# SwitchBoard.net
KiCad netlist of a schematic drawn in EAGLE
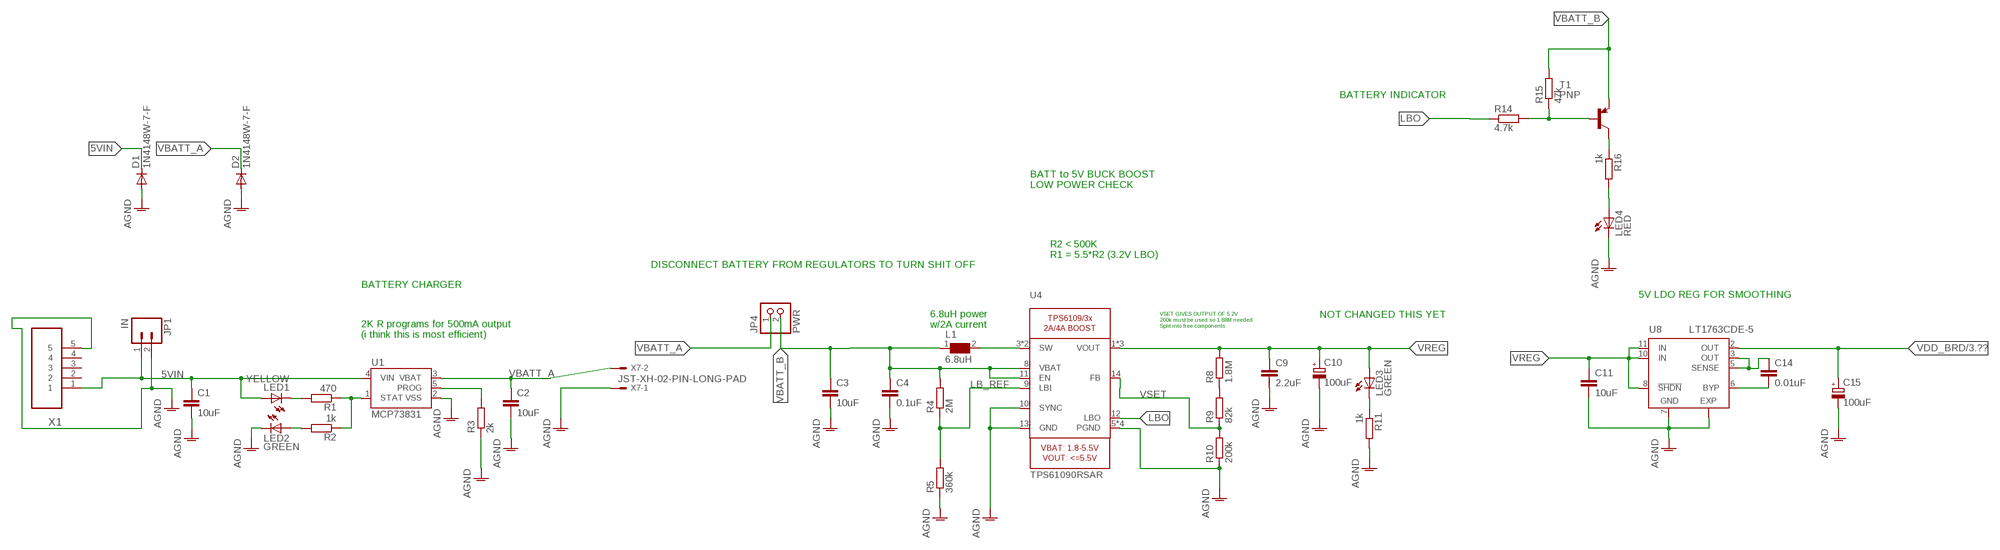
[diagram p0: schematic, sheet 1]
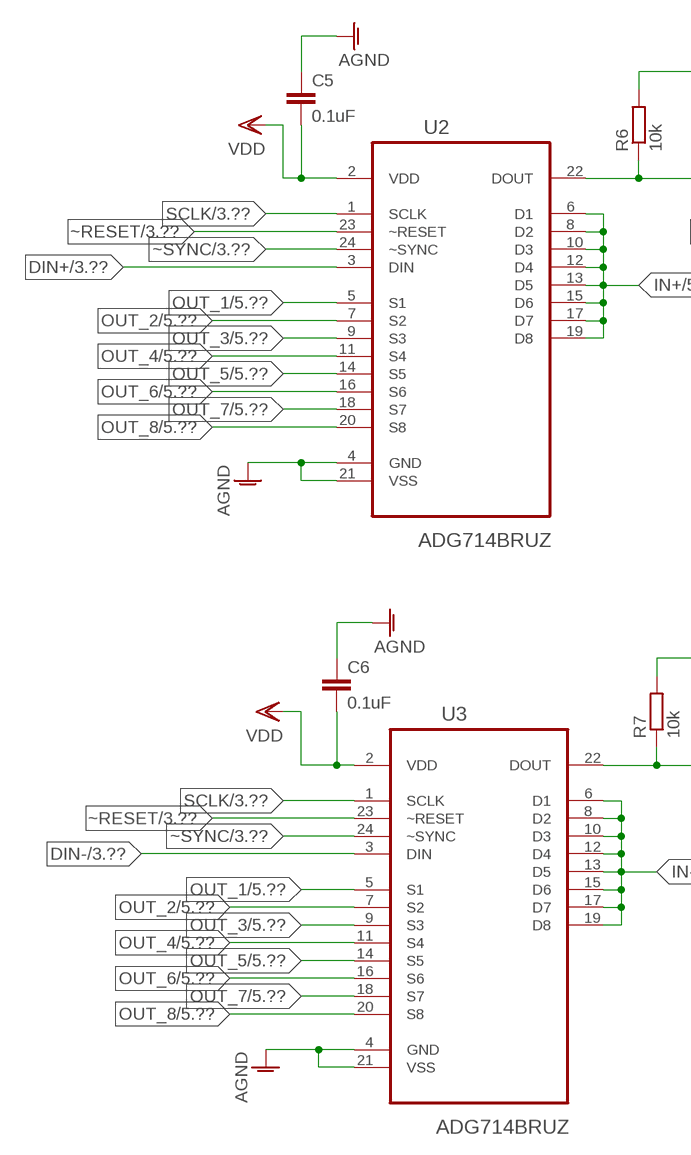
[diagram p1: schematic, sheet 2, part 1 of 2]
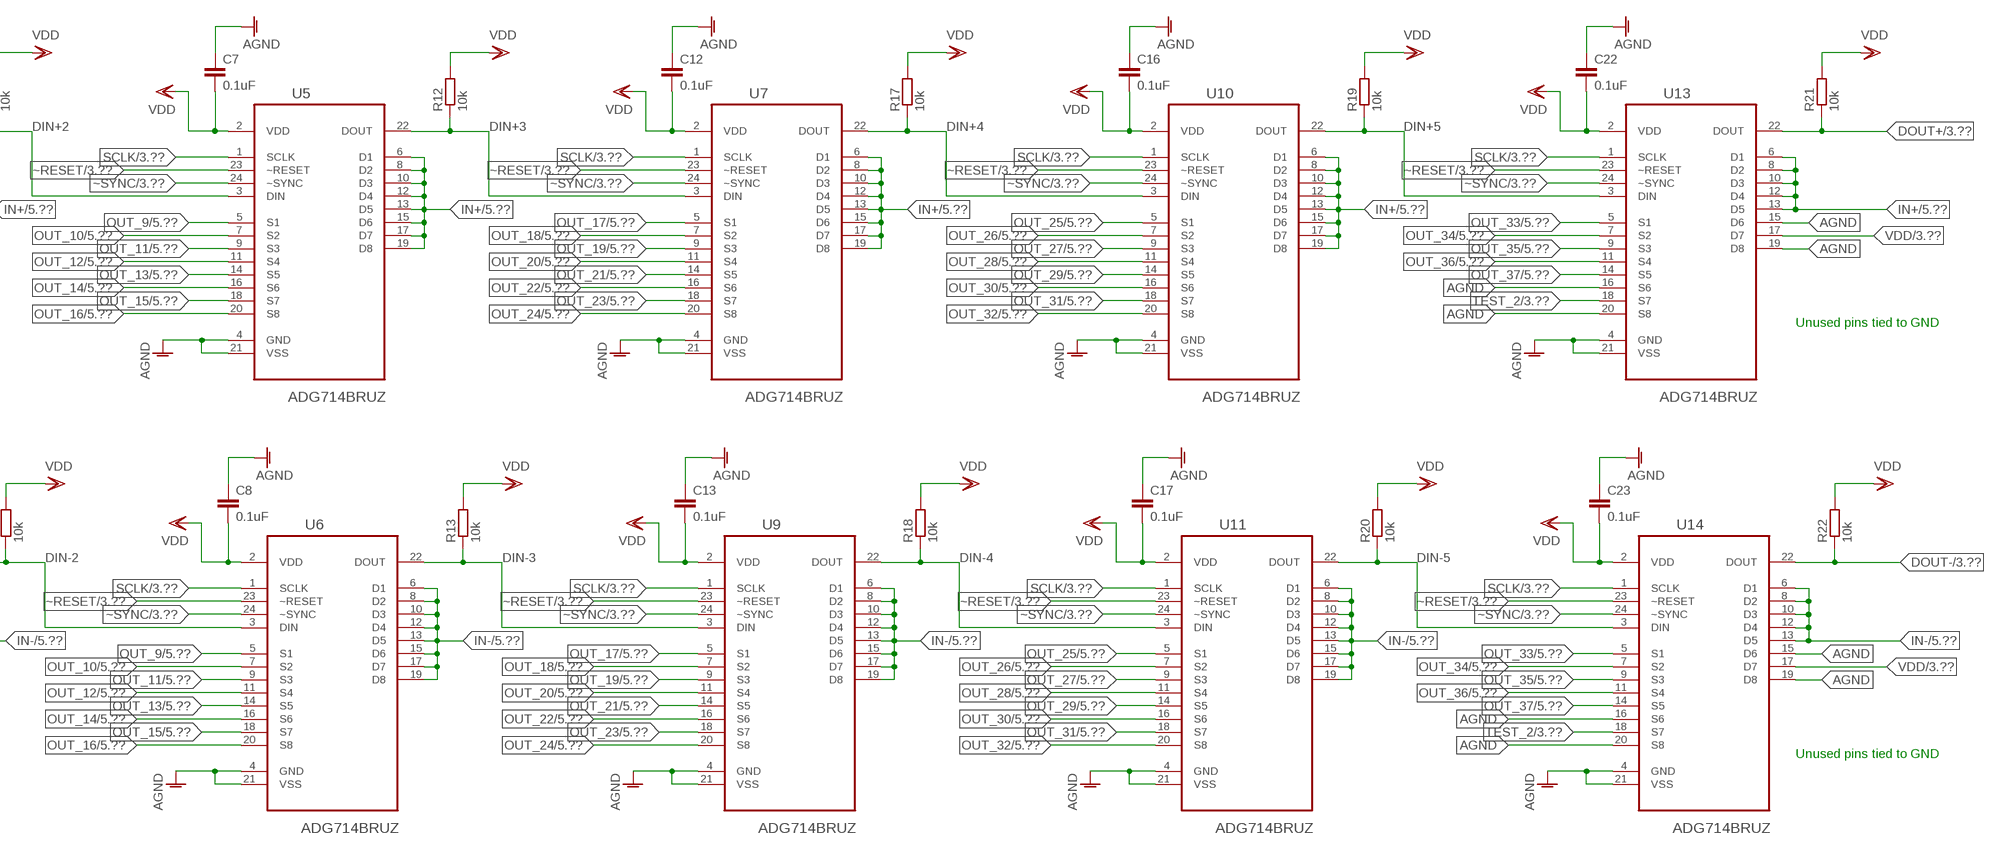
[diagram p2: schematic, sheet 2, part 2 of 2]
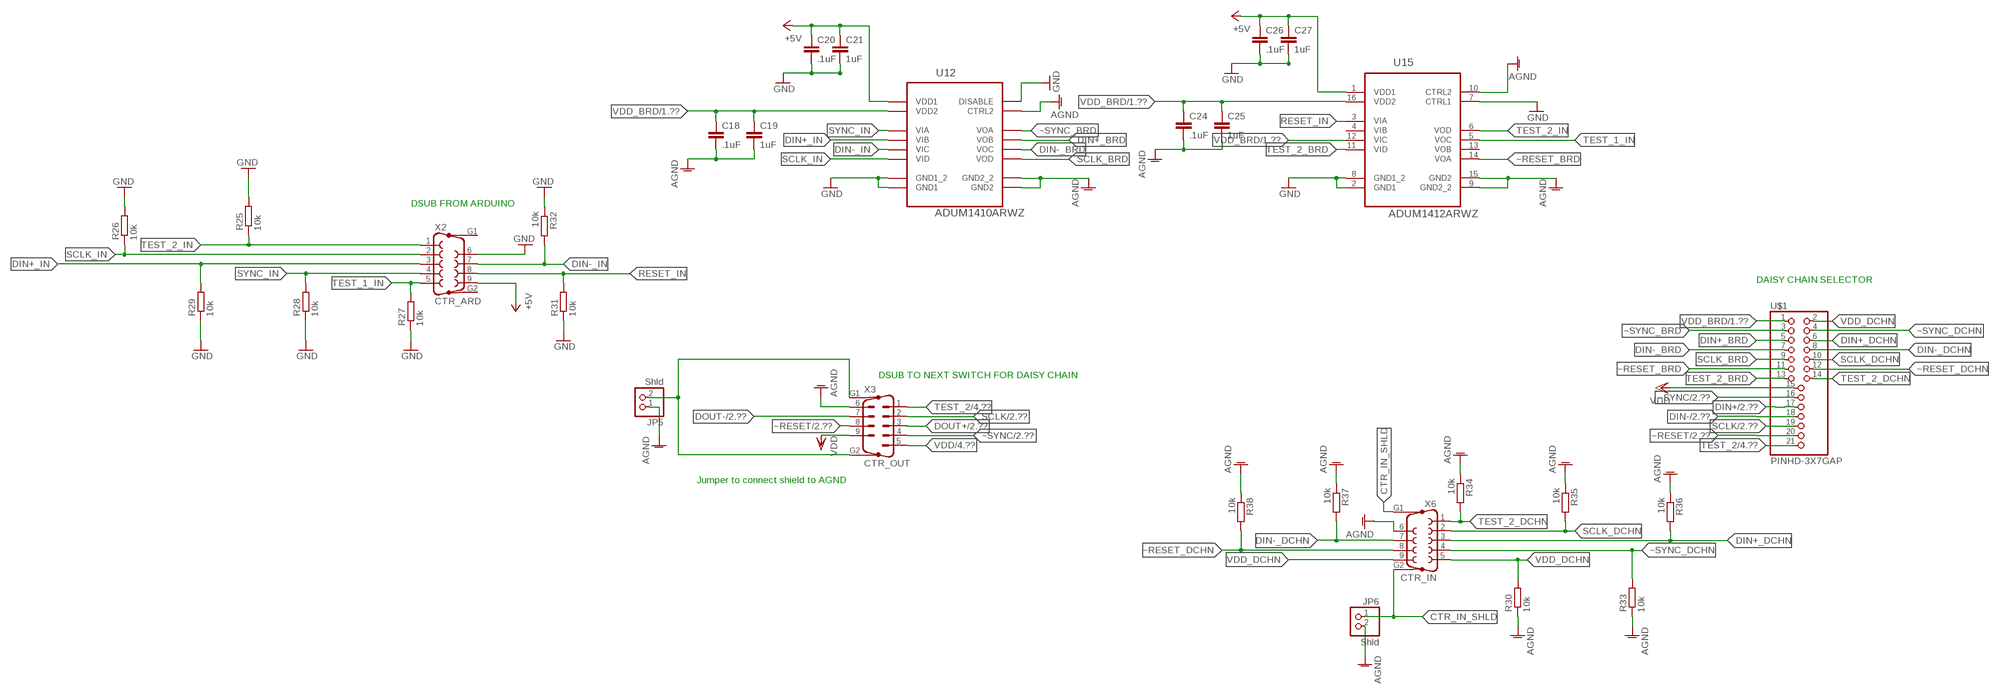
[diagram p3: schematic, sheet 3]
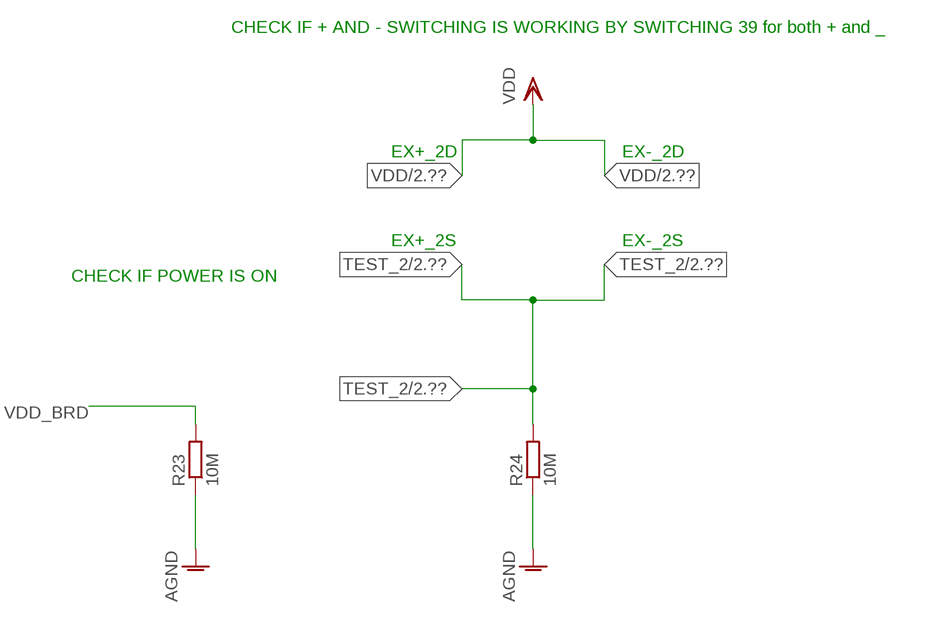
[diagram p4: schematic, sheet 4]
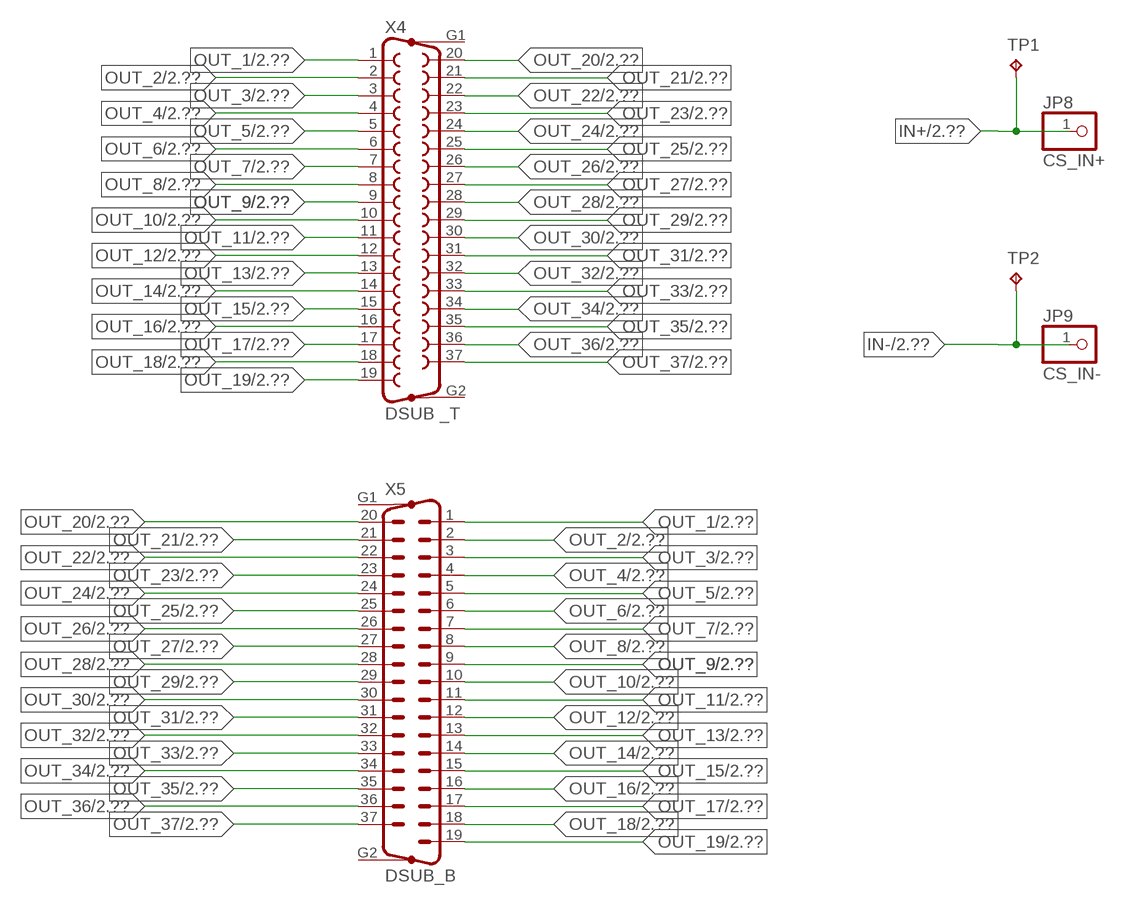
[diagram p5: schematic, sheet 5]

(export (version "E")
  (design (tool "Eeschema 10.0.6"))
  (components
    (comp (ref "JP8")
      (value "CS_IN+")
      (footprint "eagle-import:1X01")
      (libsource (lib "eagle-import") (part "PINHD-1X1"))
    )
    (comp (ref "JP9")
      (value "CS_IN-")
      (footprint "eagle-import:1X01")
      (libsource (lib "eagle-import") (part "PINHD-1X1"))
    )
    (comp (ref "TP1")
      (value "TPPAD1-20")
      (footprint "eagle-import:P1-20")
      (libsource (lib "eagle-import") (part "TPPAD1-20"))
    )
    (comp (ref "TP2")
      (value "TPPAD1-20")
      (footprint "eagle-import:P1-20")
      (libsource (lib "eagle-import") (part "TPPAD1-20"))
    )
    (comp (ref "X4")
      (value "DSUB _T")
      (footprint "eagle-import:F37HP")
      (libsource (lib "eagle-import") (part "F37HP"))
    )
    (comp (ref "X5")
      (value "DSUB_B")
      (footprint "eagle-import:M37HP")
      (libsource (lib "eagle-import") (part "M37HP"))
    )
    (comp (ref "R23")
      (value "10M")
      (footprint "eagle-import:M0805")
      (libsource (lib "eagle-import") (part "R-EU_M0805"))
    )
    (comp (ref "R24")
      (value "10M")
      (footprint "eagle-import:M0805")
      (libsource (lib "eagle-import") (part "R-EU_M0805"))
    )
    (comp (ref "C1")
      (value "10uF")
      (footprint "eagle-import:C0805")
      (libsource (lib "eagle-import") (part "C-EUC0805"))
    )
    (comp (ref "C2")
      (value "10uF")
      (footprint "eagle-import:C0805")
      (libsource (lib "eagle-import") (part "C-EUC0805"))
    )
    (comp (ref "C3")
      (value "10uF")
      (footprint "eagle-import:C0805")
      (libsource (lib "eagle-import") (part "C-EUC0805"))
    )
    (comp (ref "C4")
      (value "0.1uF")
      (footprint "eagle-import:C0805")
      (libsource (lib "eagle-import") (part "C-EUC0805"))
    )
    (comp (ref "C9")
      (value "2.2uF")
      (footprint "eagle-import:C0805")
      (libsource (lib "eagle-import") (part "C-EUC0805"))
    )
    (comp (ref "C10")
      (value "100uF")
      (footprint "eagle-import:CT6032")
      (libsource (lib "eagle-import") (part "CPOL-EUCT6032"))
    )
    (comp (ref "C11")
      (value "10uF")
      (footprint "eagle-import:C0805")
      (libsource (lib "eagle-import") (part "C-EUC0805"))
    )
    (comp (ref "C14")
      (value "0.01uF")
      (footprint "eagle-import:C0805")
      (libsource (lib "eagle-import") (part "C-EUC0805"))
    )
    (comp (ref "C15")
      (value "100uF")
      (footprint "eagle-import:CT6032")
      (libsource (lib "eagle-import") (part "CPOL-EUCT6032"))
    )
    (comp (ref "D1")
      (value "1N4148W-7-F")
      (footprint "eagle-import:SOD123")
      (libsource (lib "eagle-import") (part "DIODE-SOD123"))
    )
    (comp (ref "D2")
      (value "1N4148W-7-F")
      (footprint "eagle-import:SOD123")
      (libsource (lib "eagle-import") (part "DIODE-SOD123"))
    )
    (comp (ref "JP1")
      (value "IN")
      (footprint "eagle-import:1X02")
      (libsource (lib "eagle-import") (part "M02PTH"))
    )
    (comp (ref "JP4")
      (value "PWR")
      (footprint "eagle-import:1X02")
      (libsource (lib "eagle-import") (part "PINHD-1X2"))
    )
    (comp (ref "L1")
      (value "6.8uH")
      (footprint "eagle-import:WE-PD_7332_7345_PLASTIC_BASE")
      (fields (field (name "MPN") "7447779006"))
      (libsource (lib "eagle-import") (part "WE-PD_7332/7345_PLASTIC_BASE-7447779006"))
    )
    (comp (ref "LED1")
      (value "YELLOW")
      (footprint "eagle-import:SML0805")
      (libsource (lib "eagle-import") (part "LEDSML0805"))
    )
    (comp (ref "LED2")
      (value "GREEN")
      (footprint "eagle-import:SML0805")
      (libsource (lib "eagle-import") (part "LEDSML0805"))
    )
    (comp (ref "LED3")
      (value "GREEN")
      (footprint "eagle-import:SML0805")
      (libsource (lib "eagle-import") (part "LEDSML0805"))
    )
    (comp (ref "LED4")
      (value "RED")
      (footprint "eagle-import:SML0805")
      (libsource (lib "eagle-import") (part "LEDSML0805"))
    )
    (comp (ref "R1")
      (value "470")
      (footprint "eagle-import:M0805")
      (libsource (lib "eagle-import") (part "R-EU_M0805"))
    )
    (comp (ref "R2")
      (value "1k")
      (footprint "eagle-import:M0805")
      (libsource (lib "eagle-import") (part "R-EU_M0805"))
    )
    (comp (ref "R3")
      (value "2k")
      (footprint "eagle-import:M0805")
      (libsource (lib "eagle-import") (part "R-EU_M0805"))
    )
    (comp (ref "R4")
      (value "2M")
      (footprint "eagle-import:M0805")
      (libsource (lib "eagle-import") (part "R-EU_M0805"))
    )
    (comp (ref "R5")
      (value "360k")
      (footprint "eagle-import:M0805")
      (libsource (lib "eagle-import") (part "R-EU_M0805"))
    )
    (comp (ref "R8")
      (value "1.8M")
      (footprint "eagle-import:M0805")
      (libsource (lib "eagle-import") (part "R-EU_M0805"))
    )
    (comp (ref "R9")
      (value "82k")
      (footprint "eagle-import:M0805")
      (libsource (lib "eagle-import") (part "R-EU_M0805"))
    )
    (comp (ref "R10")
      (value "200k")
      (footprint "eagle-import:M0805")
      (libsource (lib "eagle-import") (part "R-EU_M0805"))
    )
    (comp (ref "R11")
      (value "1k")
      (footprint "eagle-import:M0805")
      (libsource (lib "eagle-import") (part "R-EU_M0805"))
    )
    (comp (ref "R14")
      (value "4.7k")
      (footprint "eagle-import:M0805")
      (libsource (lib "eagle-import") (part "R-EU_M0805"))
    )
    (comp (ref "R15")
      (value "47k")
      (footprint "eagle-import:M0805")
      (libsource (lib "eagle-import") (part "R-EU_M0805"))
    )
    (comp (ref "R16")
      (value "1k")
      (footprint "eagle-import:M0805")
      (libsource (lib "eagle-import") (part "R-EU_M0805"))
    )
    (comp (ref "T1")
      (value "PNP")
      (footprint "eagle-import:SOT23-BEC")
      (libsource (lib "eagle-import") (part "-PNP-SOT23-BECBC807-40"))
    )
    (comp (ref "U1")
      (value "MCP73831")
      (footprint "eagle-import:SOT23-5")
      (libsource (lib "eagle-import") (part "MCP73831"))
    )
    (comp (ref "U4")
      (value "TPS61090RSAR")
      (footprint "eagle-import:QFN16-4X4")
      (libsource (lib "eagle-import") (part "VREG_TPS6103XSPARKFUNVERSION"))
    )
    (comp (ref "U8")
      (value "LT1763CDE-5")
      (footprint "eagle-import:DFN12")
      (libsource (lib "eagle-import") (part "LT1763CDE-5"))
    )
    (comp (ref "X1")
      (value "47346-0001")
      (footprint "eagle-import:MOLEX_47346-0001")
      (libsource (lib "eagle-import") (part "47346-0001"))
    )
    (comp (ref "X7")
      (value "JST-XH-02-PIN-LONG-PAD")
      (footprint "eagle-import:JST-XH-02-PACKAGE-LONG-PAD")
      (libsource (lib "eagle-import") (part "JST-XH-02-PIN-LONG-PAD"))
    )
    (comp (ref "C5")
      (value "0.1uF")
      (footprint "eagle-import:C0805")
      (libsource (lib "eagle-import") (part "C-EUC0805"))
    )
    (comp (ref "C6")
      (value "0.1uF")
      (footprint "eagle-import:C0805")
      (libsource (lib "eagle-import") (part "C-EUC0805"))
    )
    (comp (ref "C7")
      (value "0.1uF")
      (footprint "eagle-import:C0805")
      (libsource (lib "eagle-import") (part "C-EUC0805"))
    )
    (comp (ref "C8")
      (value "0.1uF")
      (footprint "eagle-import:C0805")
      (libsource (lib "eagle-import") (part "C-EUC0805"))
    )
    (comp (ref "C12")
      (value "0.1uF")
      (footprint "eagle-import:C0805")
      (libsource (lib "eagle-import") (part "C-EUC0805"))
    )
    (comp (ref "C13")
      (value "0.1uF")
      (footprint "eagle-import:C0805")
      (libsource (lib "eagle-import") (part "C-EUC0805"))
    )
    (comp (ref "C16")
      (value "0.1uF")
      (footprint "eagle-import:C0805")
      (libsource (lib "eagle-import") (part "C-EUC0805"))
    )
    (comp (ref "C17")
      (value "0.1uF")
      (footprint "eagle-import:C0805")
      (libsource (lib "eagle-import") (part "C-EUC0805"))
    )
    (comp (ref "C22")
      (value "0.1uF")
      (footprint "eagle-import:C0805")
      (libsource (lib "eagle-import") (part "C-EUC0805"))
    )
    (comp (ref "C23")
      (value "0.1uF")
      (footprint "eagle-import:C0805")
      (libsource (lib "eagle-import") (part "C-EUC0805"))
    )
    (comp (ref "R6")
      (value "10k")
      (footprint "eagle-import:M0805")
      (libsource (lib "eagle-import") (part "R-EU_M0805"))
    )
    (comp (ref "R7")
      (value "10k")
      (footprint "eagle-import:M0805")
      (libsource (lib "eagle-import") (part "R-EU_M0805"))
    )
    (comp (ref "R12")
      (value "10k")
      (footprint "eagle-import:M0805")
      (libsource (lib "eagle-import") (part "R-EU_M0805"))
    )
    (comp (ref "R13")
      (value "10k")
      (footprint "eagle-import:M0805")
      (libsource (lib "eagle-import") (part "R-EU_M0805"))
    )
    (comp (ref "R17")
      (value "10k")
      (footprint "eagle-import:M0805")
      (libsource (lib "eagle-import") (part "R-EU_M0805"))
    )
    (comp (ref "R18")
      (value "10k")
      (footprint "eagle-import:M0805")
      (libsource (lib "eagle-import") (part "R-EU_M0805"))
    )
    (comp (ref "R19")
      (value "10k")
      (footprint "eagle-import:M0805")
      (libsource (lib "eagle-import") (part "R-EU_M0805"))
    )
    (comp (ref "R20")
      (value "10k")
      (footprint "eagle-import:M0805")
      (libsource (lib "eagle-import") (part "R-EU_M0805"))
    )
    (comp (ref "R21")
      (value "10k")
      (footprint "eagle-import:M0805")
      (libsource (lib "eagle-import") (part "R-EU_M0805"))
    )
    (comp (ref "R22")
      (value "10k")
      (footprint "eagle-import:M0805")
      (libsource (lib "eagle-import") (part "R-EU_M0805"))
    )
    (comp (ref "U2")
      (value "ADG714BRUZ")
      (footprint "eagle-import:SOP65P640X120-24N")
      (libsource (lib "eagle-import") (part "ADG714BRUZ"))
    )
    (comp (ref "U3")
      (value "ADG714BRUZ")
      (footprint "eagle-import:SOP65P640X120-24N")
      (libsource (lib "eagle-import") (part "ADG714BRUZ"))
    )
    (comp (ref "U5")
      (value "ADG714BRUZ")
      (footprint "eagle-import:SOP65P640X120-24N")
      (libsource (lib "eagle-import") (part "ADG714BRUZ"))
    )
    (comp (ref "U6")
      (value "ADG714BRUZ")
      (footprint "eagle-import:SOP65P640X120-24N")
      (libsource (lib "eagle-import") (part "ADG714BRUZ"))
    )
    (comp (ref "U7")
      (value "ADG714BRUZ")
      (footprint "eagle-import:SOP65P640X120-24N")
      (libsource (lib "eagle-import") (part "ADG714BRUZ"))
    )
    (comp (ref "U9")
      (value "ADG714BRUZ")
      (footprint "eagle-import:SOP65P640X120-24N")
      (libsource (lib "eagle-import") (part "ADG714BRUZ"))
    )
    (comp (ref "U10")
      (value "ADG714BRUZ")
      (footprint "eagle-import:SOP65P640X120-24N")
      (libsource (lib "eagle-import") (part "ADG714BRUZ"))
    )
    (comp (ref "U11")
      (value "ADG714BRUZ")
      (footprint "eagle-import:SOP65P640X120-24N")
      (libsource (lib "eagle-import") (part "ADG714BRUZ"))
    )
    (comp (ref "U13")
      (value "ADG714BRUZ")
      (footprint "eagle-import:SOP65P640X120-24N")
      (libsource (lib "eagle-import") (part "ADG714BRUZ"))
    )
    (comp (ref "U14")
      (value "ADG714BRUZ")
      (footprint "eagle-import:SOP65P640X120-24N")
      (libsource (lib "eagle-import") (part "ADG714BRUZ"))
    )
    (comp (ref "C18")
      (value ".1uF")
      (footprint "eagle-import:C0805")
      (libsource (lib "eagle-import") (part "C-EUC0805"))
    )
    (comp (ref "C19")
      (value "1uF")
      (footprint "eagle-import:C0805")
      (libsource (lib "eagle-import") (part "C-EUC0805"))
    )
    (comp (ref "C20")
      (value ".1uF")
      (footprint "eagle-import:C0805")
      (libsource (lib "eagle-import") (part "C-EUC0805"))
    )
    (comp (ref "C21")
      (value "1uF")
      (footprint "eagle-import:C0805")
      (libsource (lib "eagle-import") (part "C-EUC0805"))
    )
    (comp (ref "C24")
      (value ".1uF")
      (footprint "eagle-import:C0805")
      (libsource (lib "eagle-import") (part "C-EUC0805"))
    )
    (comp (ref "C25")
      (value "1uF")
      (footprint "eagle-import:C0805")
      (libsource (lib "eagle-import") (part "C-EUC0805"))
    )
    (comp (ref "C26")
      (value ".1uF")
      (footprint "eagle-import:C0805")
      (libsource (lib "eagle-import") (part "C-EUC0805"))
    )
    (comp (ref "C27")
      (value "1uF")
      (footprint "eagle-import:C0805")
      (libsource (lib "eagle-import") (part "C-EUC0805"))
    )
    (comp (ref "JP5")
      (value "Shld")
      (footprint "eagle-import:1X02")
      (libsource (lib "eagle-import") (part "PINHD-1X2"))
    )
    (comp (ref "JP6")
      (value "Shld")
      (footprint "eagle-import:1X02")
      (libsource (lib "eagle-import") (part "PINHD-1X2"))
    )
    (comp (ref "R25")
      (value "10k")
      (footprint "eagle-import:R0402")
      (libsource (lib "eagle-import") (part "R-EU_R0402"))
    )
    (comp (ref "R26")
      (value "10k")
      (footprint "eagle-import:R0402")
      (libsource (lib "eagle-import") (part "R-EU_R0402"))
    )
    (comp (ref "R27")
      (value "10k")
      (footprint "eagle-import:R0402")
      (libsource (lib "eagle-import") (part "R-EU_R0402"))
    )
    (comp (ref "R28")
      (value "10k")
      (footprint "eagle-import:R0402")
      (libsource (lib "eagle-import") (part "R-EU_R0402"))
    )
    (comp (ref "R29")
      (value "10k")
      (footprint "eagle-import:R0402")
      (libsource (lib "eagle-import") (part "R-EU_R0402"))
    )
    (comp (ref "R30")
      (value "10k")
      (footprint "eagle-import:R0402")
      (libsource (lib "eagle-import") (part "R-EU_R0402"))
    )
    (comp (ref "R31")
      (value "10k")
      (footprint "eagle-import:R0402")
      (libsource (lib "eagle-import") (part "R-EU_R0402"))
    )
    (comp (ref "R32")
      (value "10k")
      (footprint "eagle-import:R0402")
      (libsource (lib "eagle-import") (part "R-EU_R0402"))
    )
    (comp (ref "R33")
      (value "10k")
      (footprint "eagle-import:R0402")
      (libsource (lib "eagle-import") (part "R-EU_R0402"))
    )
    (comp (ref "R34")
      (value "10k")
      (footprint "eagle-import:R0402")
      (libsource (lib "eagle-import") (part "R-EU_R0402"))
    )
    (comp (ref "R35")
      (value "10k")
      (footprint "eagle-import:R0402")
      (libsource (lib "eagle-import") (part "R-EU_R0402"))
    )
    (comp (ref "R36")
      (value "10k")
      (footprint "eagle-import:R0402")
      (libsource (lib "eagle-import") (part "R-EU_R0402"))
    )
    (comp (ref "R37")
      (value "10k")
      (footprint "eagle-import:R0402")
      (libsource (lib "eagle-import") (part "R-EU_R0402"))
    )
    (comp (ref "R38")
      (value "10k")
      (footprint "eagle-import:R0402")
      (libsource (lib "eagle-import") (part "R-EU_R0402"))
    )
    (comp (ref "U$1")
      (value "PINHD-3X7GAP")
      (footprint "eagle-import:3X07")
      (libsource (lib "eagle-import") (part "PINHD-3X7GAP"))
    )
    (comp (ref "U12")
      (value "ADUM1410ARWZ")
      (footprint "eagle-import:SOIC127P1032X265-16N")
      (libsource (lib "eagle-import") (part "ADUM1410ARWZ"))
    )
    (comp (ref "U15")
      (value "ADUM1412ARWZ")
      (footprint "eagle-import:SOIC127P1032X265-16N")
      (libsource (lib "eagle-import") (part "ADUM1412ARWZ"))
    )
    (comp (ref "X2")
      (value "CTR_ARD")
      (footprint "eagle-import:F09HP")
      (libsource (lib "eagle-import") (part "F09HP"))
    )
    (comp (ref "X3")
      (value "CTR_OUT")
      (footprint "eagle-import:M09HP")
      (libsource (lib "eagle-import") (part "M09HP"))
    )
    (comp (ref "X6")
      (value "CTR_IN")
      (footprint "eagle-import:F09HP")
      (libsource (lib "eagle-import") (part "F09HP"))
    )
  )
  (nets
    (net (code "1") (name "+5V") (class "Default")
      (node (ref "C20") (pin "1") (pinfunction "1_1") (pintype "passive"))
      (node (ref "C21") (pin "1") (pinfunction "1_1") (pintype "passive"))
      (node (ref "C26") (pin "1") (pinfunction "1_1") (pintype "passive"))
      (node (ref "C27") (pin "1") (pinfunction "1_1") (pintype "passive"))
      (node (ref "U12") (pin "1") (pinfunction "VDD1_1") (pintype "power_in"))
      (node (ref "U15") (pin "1") (pinfunction "VDD1_1") (pintype "power_in"))
      (node (ref "X2") (pin "9") (pinfunction "9_9") (pintype "passive"))
    )
    (net (code "2") (name "5VIN") (class "Default")
      (node (ref "C1") (pin "1") (pinfunction "1_1") (pintype "passive"))
      (node (ref "D1") (pin "C") (pinfunction "C_C") (pintype "passive"))
      (node (ref "JP1") (pin "1") (pinfunction "1_1") (pintype "passive"))
      (node (ref "LED1") (pin "A") (pinfunction "A_A") (pintype "passive"))
      (node (ref "U1") (pin "4") (pinfunction "VIN_4") (pintype "power_in"))
      (node (ref "X1") (pin "1") (pinfunction "1_1") (pintype "input"))
    )
    (net (code "3") (name "AGND") (class "Default")
      (node (ref "C1") (pin "2") (pinfunction "2_2") (pintype "passive"))
      (node (ref "C10") (pin "-") (pinfunction "-_-") (pintype "passive"))
      (node (ref "C11") (pin "2") (pinfunction "2_2") (pintype "passive"))
      (node (ref "C12") (pin "1") (pinfunction "1_1") (pintype "passive"))
      (node (ref "C13") (pin "1") (pinfunction "1_1") (pintype "passive"))
      (node (ref "C15") (pin "-") (pinfunction "-_-") (pintype "passive"))
      (node (ref "C16") (pin "1") (pinfunction "1_1") (pintype "passive"))
      (node (ref "C17") (pin "1") (pinfunction "1_1") (pintype "passive"))
      (node (ref "C18") (pin "2") (pinfunction "2_2") (pintype "passive"))
      (node (ref "C19") (pin "2") (pinfunction "2_2") (pintype "passive"))
      (node (ref "C2") (pin "2") (pinfunction "2_2") (pintype "passive"))
      (node (ref "C22") (pin "1") (pinfunction "1_1") (pintype "passive"))
      (node (ref "C23") (pin "1") (pinfunction "1_1") (pintype "passive"))
      (node (ref "C24") (pin "2") (pinfunction "2_2") (pintype "passive"))
      (node (ref "C25") (pin "2") (pinfunction "2_2") (pintype "passive"))
      (node (ref "C3") (pin "2") (pinfunction "2_2") (pintype "passive"))
      (node (ref "C4") (pin "2") (pinfunction "2_2") (pintype "passive"))
      (node (ref "C5") (pin "1") (pinfunction "1_1") (pintype "passive"))
      (node (ref "C6") (pin "1") (pinfunction "1_1") (pintype "passive"))
      (node (ref "C7") (pin "1") (pinfunction "1_1") (pintype "passive"))
      (node (ref "C8") (pin "1") (pinfunction "1_1") (pintype "passive"))
      (node (ref "C9") (pin "2") (pinfunction "2_2") (pintype "passive"))
      (node (ref "D1") (pin "A") (pinfunction "A_A") (pintype "passive"))
      (node (ref "D2") (pin "A") (pinfunction "A_A") (pintype "passive"))
      (node (ref "JP1") (pin "2") (pinfunction "2_2") (pintype "passive"))
      (node (ref "JP5") (pin "1") (pinfunction "1_1") (pintype "passive"))
      (node (ref "JP6") (pin "2") (pinfunction "2_2") (pintype "passive"))
      (node (ref "LED2") (pin "C") (pinfunction "C_C") (pintype "passive"))
      (node (ref "LED4") (pin "C") (pinfunction "C_C") (pintype "passive"))
      (node (ref "R10") (pin "1") (pinfunction "1_1") (pintype "passive"))
      (node (ref "R11") (pin "2") (pinfunction "2_2") (pintype "passive"))
      (node (ref "R23") (pin "1") (pinfunction "1_1") (pintype "passive"))
      (node (ref "R24") (pin "1") (pinfunction "1_1") (pintype "passive"))
      (node (ref "R3") (pin "1") (pinfunction "1_1") (pintype "passive"))
      (node (ref "R30") (pin "1") (pinfunction "1_1") (pintype "passive"))
      (node (ref "R33") (pin "1") (pinfunction "1_1") (pintype "passive"))
      (node (ref "R34") (pin "1") (pinfunction "1_1") (pintype "passive"))
      (node (ref "R35") (pin "1") (pinfunction "1_1") (pintype "passive"))
      (node (ref "R36") (pin "1") (pinfunction "1_1") (pintype "passive"))
      (node (ref "R37") (pin "1") (pinfunction "1_1") (pintype "passive"))
      (node (ref "R38") (pin "1") (pinfunction "1_1") (pintype "passive"))
      (node (ref "R5") (pin "1") (pinfunction "1_1") (pintype "passive"))
      (node (ref "U1") (pin "2") (pinfunction "VSS_2") (pintype "power_in"))
      (node (ref "U10") (pin "21") (pinfunction "VSS_21") (pintype "power_in"))
      (node (ref "U10") (pin "4") (pinfunction "GND_4") (pintype "passive"))
      (node (ref "U11") (pin "21") (pinfunction "VSS_21") (pintype "power_in"))
      (node (ref "U11") (pin "4") (pinfunction "GND_4") (pintype "passive"))
      (node (ref "U12") (pin "10") (pinfunction "CTRL2_10") (pintype "passive"))
      (node (ref "U12") (pin "15") (pinfunction "GND2_15") (pintype "passive"))
      (node (ref "U12") (pin "9") (pinfunction "GND2_2_9") (pintype "passive"))
      (node (ref "U13") (pin "15") (pinfunction "D6_15") (pintype "bidirectional"))
      (node (ref "U13") (pin "16") (pinfunction "S6_16") (pintype "bidirectional"))
      (node (ref "U13") (pin "19") (pinfunction "D8_19") (pintype "bidirectional"))
      (node (ref "U13") (pin "20") (pinfunction "S8_20") (pintype "bidirectional"))
      (node (ref "U13") (pin "21") (pinfunction "VSS_21") (pintype "power_in"))
      (node (ref "U13") (pin "4") (pinfunction "GND_4") (pintype "passive"))
      (node (ref "U14") (pin "15") (pinfunction "D6_15") (pintype "bidirectional"))
      (node (ref "U14") (pin "16") (pinfunction "S6_16") (pintype "bidirectional"))
      (node (ref "U14") (pin "19") (pinfunction "D8_19") (pintype "bidirectional"))
      (node (ref "U14") (pin "20") (pinfunction "S8_20") (pintype "bidirectional"))
      (node (ref "U14") (pin "21") (pinfunction "VSS_21") (pintype "power_in"))
      (node (ref "U14") (pin "4") (pinfunction "GND_4") (pintype "passive"))
      (node (ref "U15") (pin "10") (pinfunction "CTRL2_10") (pintype "passive"))
      (node (ref "U15") (pin "15") (pinfunction "GND2_15") (pintype "passive"))
      (node (ref "U15") (pin "9") (pinfunction "GND2_2_9") (pintype "passive"))
      (node (ref "U2") (pin "21") (pinfunction "VSS_21") (pintype "power_in"))
      (node (ref "U2") (pin "4") (pinfunction "GND_4") (pintype "passive"))
      (node (ref "U3") (pin "21") (pinfunction "VSS_21") (pintype "power_in"))
      (node (ref "U3") (pin "4") (pinfunction "GND_4") (pintype "passive"))
      (node (ref "U4") (pin "10") (pinfunction "SYNC_10") (pintype "input"))
      (node (ref "U4") (pin "13") (pinfunction "GND_13") (pintype "power_in"))
      (node (ref "U4") (pin "5") (pinfunction "PGND_5") (pintype "power_in"))
      (node (ref "U4") (pin "6") (pinfunction "PGND_6") (pintype "power_in"))
      (node (ref "U4") (pin "7") (pinfunction "PGND_7") (pintype "power_in"))
      (node (ref "U4") (pin "EXP") (pinfunction "PGND_EXP") (pintype "power_in"))
      (node (ref "U5") (pin "21") (pinfunction "VSS_21") (pintype "power_in"))
      (node (ref "U5") (pin "4") (pinfunction "GND_4") (pintype "passive"))
      (node (ref "U6") (pin "21") (pinfunction "VSS_21") (pintype "power_in"))
      (node (ref "U6") (pin "4") (pinfunction "GND_4") (pintype "passive"))
      (node (ref "U7") (pin "21") (pinfunction "VSS_21") (pintype "power_in"))
      (node (ref "U7") (pin "4") (pinfunction "GND_4") (pintype "passive"))
      (node (ref "U8") (pin "7") (pinfunction "GND_7") (pintype "power_in"))
      (node (ref "U8") (pin "EXP") (pinfunction "EXP_EXP") (pintype "power_in"))
      (node (ref "U9") (pin "21") (pinfunction "VSS_21") (pintype "power_in"))
      (node (ref "U9") (pin "4") (pinfunction "GND_4") (pintype "passive"))
      (node (ref "X1") (pin "5") (pinfunction "5_5") (pintype "input"))
      (node (ref "X3") (pin "6") (pinfunction "6_6") (pintype "passive"))
      (node (ref "X6") (pin "6") (pinfunction "6_6") (pintype "passive"))
      (node (ref "X7") (pin "1") (pinfunction "S_1") (pintype "passive"))
    )
    (net (code "4") (name "CTR_IN_SHLD") (class "Default")
      (node (ref "JP6") (pin "1") (pinfunction "1_1") (pintype "passive"))
      (node (ref "X6") (pin "G1") (pinfunction "G1_G1") (pintype "passive"))
      (node (ref "X6") (pin "G2") (pinfunction "G2_G2") (pintype "passive"))
    )
    (net (code "5") (name "DIN+") (class "Default")
      (node (ref "U$1") (pin "17") (pinfunction "17_17") (pintype "passive"))
      (node (ref "U2") (pin "3") (pinfunction "DIN_3") (pintype "input"))
    )
    (net (code "6") (name "DIN+2") (class "Default")
      (node (ref "R6") (pin "1") (pinfunction "1_1") (pintype "passive"))
      (node (ref "U2") (pin "22") (pinfunction "DOUT_22") (pintype "output"))
      (node (ref "U5") (pin "3") (pinfunction "DIN_3") (pintype "input"))
    )
    (net (code "7") (name "DIN+3") (class "Default")
      (node (ref "R12") (pin "1") (pinfunction "1_1") (pintype "passive"))
      (node (ref "U5") (pin "22") (pinfunction "DOUT_22") (pintype "output"))
      (node (ref "U7") (pin "3") (pinfunction "DIN_3") (pintype "input"))
    )
    (net (code "8") (name "DIN+4") (class "Default")
      (node (ref "R17") (pin "1") (pinfunction "1_1") (pintype "passive"))
      (node (ref "U10") (pin "3") (pinfunction "DIN_3") (pintype "input"))
      (node (ref "U7") (pin "22") (pinfunction "DOUT_22") (pintype "output"))
    )
    (net (code "9") (name "DIN+5") (class "Default")
      (node (ref "R19") (pin "1") (pinfunction "1_1") (pintype "passive"))
      (node (ref "U10") (pin "22") (pinfunction "DOUT_22") (pintype "output"))
      (node (ref "U13") (pin "3") (pinfunction "DIN_3") (pintype "input"))
    )
    (net (code "10") (name "DIN+_BRD") (class "Default")
      (node (ref "U$1") (pin "5") (pinfunction "5_5") (pintype "passive"))
      (node (ref "U12") (pin "13") (pinfunction "VOB_13") (pintype "passive"))
    )
    (net (code "11") (name "DIN+_DCHN") (class "Default")
      (node (ref "R36") (pin "2") (pinfunction "2_2") (pintype "passive"))
      (node (ref "U$1") (pin "6") (pinfunction "6_6") (pintype "passive"))
      (node (ref "X6") (pin "3") (pinfunction "3_3") (pintype "passive"))
    )
    (net (code "12") (name "DIN+_IN") (class "Default")
      (node (ref "R29") (pin "2") (pinfunction "2_2") (pintype "passive"))
      (node (ref "U12") (pin "4") (pinfunction "VIB_4") (pintype "passive"))
      (node (ref "X2") (pin "3") (pinfunction "3_3") (pintype "passive"))
    )
    (net (code "13") (name "DIN-") (class "Default")
      (node (ref "U$1") (pin "18") (pinfunction "18_18") (pintype "passive"))
      (node (ref "U3") (pin "3") (pinfunction "DIN_3") (pintype "input"))
    )
    (net (code "14") (name "DIN-2") (class "Default")
      (node (ref "R7") (pin "1") (pinfunction "1_1") (pintype "passive"))
      (node (ref "U3") (pin "22") (pinfunction "DOUT_22") (pintype "output"))
      (node (ref "U6") (pin "3") (pinfunction "DIN_3") (pintype "input"))
    )
    (net (code "15") (name "DIN-3") (class "Default")
      (node (ref "R13") (pin "1") (pinfunction "1_1") (pintype "passive"))
      (node (ref "U6") (pin "22") (pinfunction "DOUT_22") (pintype "output"))
      (node (ref "U9") (pin "3") (pinfunction "DIN_3") (pintype "input"))
    )
    (net (code "16") (name "DIN-4") (class "Default")
      (node (ref "R18") (pin "1") (pinfunction "1_1") (pintype "passive"))
      (node (ref "U11") (pin "3") (pinfunction "DIN_3") (pintype "input"))
      (node (ref "U9") (pin "22") (pinfunction "DOUT_22") (pintype "output"))
    )
    (net (code "17") (name "DIN-5") (class "Default")
      (node (ref "R20") (pin "1") (pinfunction "1_1") (pintype "passive"))
      (node (ref "U11") (pin "22") (pinfunction "DOUT_22") (pintype "output"))
      (node (ref "U14") (pin "3") (pinfunction "DIN_3") (pintype "input"))
    )
    (net (code "18") (name "DIN-_BRD") (class "Default")
      (node (ref "U$1") (pin "7") (pinfunction "7_7") (pintype "passive"))
      (node (ref "U12") (pin "12") (pinfunction "VOC_12") (pintype "passive"))
    )
    (net (code "19") (name "DIN-_DCHN") (class "Default")
      (node (ref "R37") (pin "2") (pinfunction "2_2") (pintype "passive"))
      (node (ref "U$1") (pin "8") (pinfunction "8_8") (pintype "passive"))
      (node (ref "X6") (pin "7") (pinfunction "7_7") (pintype "passive"))
    )
    (net (code "20") (name "DIN-_IN") (class "Default")
      (node (ref "R32") (pin "2") (pinfunction "2_2") (pintype "passive"))
      (node (ref "U12") (pin "5") (pinfunction "VIC_5") (pintype "passive"))
      (node (ref "X2") (pin "7") (pinfunction "7_7") (pintype "passive"))
    )
    (net (code "21") (name "DOUT+") (class "Default")
      (node (ref "R21") (pin "1") (pinfunction "1_1") (pintype "passive"))
      (node (ref "U13") (pin "22") (pinfunction "DOUT_22") (pintype "output"))
      (node (ref "X3") (pin "3") (pinfunction "3_3") (pintype "passive"))
    )
    (net (code "22") (name "DOUT-") (class "Default")
      (node (ref "R22") (pin "1") (pinfunction "1_1") (pintype "passive"))
      (node (ref "U14") (pin "22") (pinfunction "DOUT_22") (pintype "output"))
      (node (ref "X3") (pin "7") (pinfunction "7_7") (pintype "passive"))
    )
    (net (code "23") (name "GND") (class "Default")
      (node (ref "C20") (pin "2") (pinfunction "2_2") (pintype "passive"))
      (node (ref "C21") (pin "2") (pinfunction "2_2") (pintype "passive"))
      (node (ref "C26") (pin "2") (pinfunction "2_2") (pintype "passive"))
      (node (ref "C27") (pin "2") (pinfunction "2_2") (pintype "passive"))
      (node (ref "R25") (pin "2") (pinfunction "2_2") (pintype "passive"))
      (node (ref "R26") (pin "2") (pinfunction "2_2") (pintype "passive"))
      (node (ref "R27") (pin "1") (pinfunction "1_1") (pintype "passive"))
      (node (ref "R28") (pin "1") (pinfunction "1_1") (pintype "passive"))
      (node (ref "R29") (pin "1") (pinfunction "1_1") (pintype "passive"))
      (node (ref "R31") (pin "1") (pinfunction "1_1") (pintype "passive"))
      (node (ref "R32") (pin "1") (pinfunction "1_1") (pintype "passive"))
      (node (ref "U12") (pin "2") (pinfunction "GND1_2_2") (pintype "passive"))
      (node (ref "U12") (pin "7") (pinfunction "DISABLE_7") (pintype "passive"))
      (node (ref "U12") (pin "8") (pinfunction "GND1_8") (pintype "passive"))
      (node (ref "U15") (pin "2") (pinfunction "GND1_2") (pintype "passive"))
      (node (ref "U15") (pin "7") (pinfunction "CTRL1_7") (pintype "passive"))
      (node (ref "U15") (pin "8") (pinfunction "GND1_2_8") (pintype "passive"))
      (node (ref "X2") (pin "6") (pinfunction "6_6") (pintype "passive"))
    )
    (net (code "24") (name "IN+") (class "Default")
      (node (ref "JP8") (pin "1") (pinfunction "1_1") (pintype "passive"))
      (node (ref "TP1") (pin "TP") (pinfunction "TP_TP") (pintype "input"))
      (node (ref "U10") (pin "10") (pinfunction "D3_10") (pintype "bidirectional"))
      (node (ref "U10") (pin "12") (pinfunction "D4_12") (pintype "bidirectional"))
      (node (ref "U10") (pin "13") (pinfunction "D5_13") (pintype "bidirectional"))
      (node (ref "U10") (pin "15") (pinfunction "D6_15") (pintype "bidirectional"))
      (node (ref "U10") (pin "17") (pinfunction "D7_17") (pintype "bidirectional"))
      (node (ref "U10") (pin "19") (pinfunction "D8_19") (pintype "bidirectional"))
      (node (ref "U10") (pin "6") (pinfunction "D1_6") (pintype "bidirectional"))
      (node (ref "U10") (pin "8") (pinfunction "D2_8") (pintype "bidirectional"))
      (node (ref "U13") (pin "10") (pinfunction "D3_10") (pintype "bidirectional"))
      (node (ref "U13") (pin "12") (pinfunction "D4_12") (pintype "bidirectional"))
      (node (ref "U13") (pin "13") (pinfunction "D5_13") (pintype "bidirectional"))
      (node (ref "U13") (pin "6") (pinfunction "D1_6") (pintype "bidirectional"))
      (node (ref "U13") (pin "8") (pinfunction "D2_8") (pintype "bidirectional"))
      (node (ref "U2") (pin "10") (pinfunction "D3_10") (pintype "bidirectional"))
      (node (ref "U2") (pin "12") (pinfunction "D4_12") (pintype "bidirectional"))
      (node (ref "U2") (pin "13") (pinfunction "D5_13") (pintype "bidirectional"))
      (node (ref "U2") (pin "15") (pinfunction "D6_15") (pintype "bidirectional"))
      (node (ref "U2") (pin "17") (pinfunction "D7_17") (pintype "bidirectional"))
      (node (ref "U2") (pin "19") (pinfunction "D8_19") (pintype "bidirectional"))
      (node (ref "U2") (pin "6") (pinfunction "D1_6") (pintype "bidirectional"))
      (node (ref "U2") (pin "8") (pinfunction "D2_8") (pintype "bidirectional"))
      (node (ref "U5") (pin "10") (pinfunction "D3_10") (pintype "bidirectional"))
      (node (ref "U5") (pin "12") (pinfunction "D4_12") (pintype "bidirectional"))
      (node (ref "U5") (pin "13") (pinfunction "D5_13") (pintype "bidirectional"))
      (node (ref "U5") (pin "15") (pinfunction "D6_15") (pintype "bidirectional"))
      (node (ref "U5") (pin "17") (pinfunction "D7_17") (pintype "bidirectional"))
      (node (ref "U5") (pin "19") (pinfunction "D8_19") (pintype "bidirectional"))
      (node (ref "U5") (pin "6") (pinfunction "D1_6") (pintype "bidirectional"))
      (node (ref "U5") (pin "8") (pinfunction "D2_8") (pintype "bidirectional"))
      (node (ref "U7") (pin "10") (pinfunction "D3_10") (pintype "bidirectional"))
      (node (ref "U7") (pin "12") (pinfunction "D4_12") (pintype "bidirectional"))
      (node (ref "U7") (pin "13") (pinfunction "D5_13") (pintype "bidirectional"))
      (node (ref "U7") (pin "15") (pinfunction "D6_15") (pintype "bidirectional"))
      (node (ref "U7") (pin "17") (pinfunction "D7_17") (pintype "bidirectional"))
      (node (ref "U7") (pin "19") (pinfunction "D8_19") (pintype "bidirectional"))
      (node (ref "U7") (pin "6") (pinfunction "D1_6") (pintype "bidirectional"))
      (node (ref "U7") (pin "8") (pinfunction "D2_8") (pintype "bidirectional"))
    )
    (net (code "25") (name "IN-") (class "Default")
      (node (ref "JP9") (pin "1") (pinfunction "1_1") (pintype "passive"))
      (node (ref "TP2") (pin "TP") (pinfunction "TP_TP") (pintype "input"))
      (node (ref "U11") (pin "10") (pinfunction "D3_10") (pintype "bidirectional"))
      (node (ref "U11") (pin "12") (pinfunction "D4_12") (pintype "bidirectional"))
      (node (ref "U11") (pin "13") (pinfunction "D5_13") (pintype "bidirectional"))
      (node (ref "U11") (pin "15") (pinfunction "D6_15") (pintype "bidirectional"))
      (node (ref "U11") (pin "17") (pinfunction "D7_17") (pintype "bidirectional"))
      (node (ref "U11") (pin "19") (pinfunction "D8_19") (pintype "bidirectional"))
      (node (ref "U11") (pin "6") (pinfunction "D1_6") (pintype "bidirectional"))
      (node (ref "U11") (pin "8") (pinfunction "D2_8") (pintype "bidirectional"))
      (node (ref "U14") (pin "10") (pinfunction "D3_10") (pintype "bidirectional"))
      (node (ref "U14") (pin "12") (pinfunction "D4_12") (pintype "bidirectional"))
      (node (ref "U14") (pin "13") (pinfunction "D5_13") (pintype "bidirectional"))
      (node (ref "U14") (pin "6") (pinfunction "D1_6") (pintype "bidirectional"))
      (node (ref "U14") (pin "8") (pinfunction "D2_8") (pintype "bidirectional"))
      (node (ref "U3") (pin "10") (pinfunction "D3_10") (pintype "bidirectional"))
      (node (ref "U3") (pin "12") (pinfunction "D4_12") (pintype "bidirectional"))
      (node (ref "U3") (pin "13") (pinfunction "D5_13") (pintype "bidirectional"))
      (node (ref "U3") (pin "15") (pinfunction "D6_15") (pintype "bidirectional"))
      (node (ref "U3") (pin "17") (pinfunction "D7_17") (pintype "bidirectional"))
      (node (ref "U3") (pin "19") (pinfunction "D8_19") (pintype "bidirectional"))
      (node (ref "U3") (pin "6") (pinfunction "D1_6") (pintype "bidirectional"))
      (node (ref "U3") (pin "8") (pinfunction "D2_8") (pintype "bidirectional"))
      (node (ref "U6") (pin "10") (pinfunction "D3_10") (pintype "bidirectional"))
      (node (ref "U6") (pin "12") (pinfunction "D4_12") (pintype "bidirectional"))
      (node (ref "U6") (pin "13") (pinfunction "D5_13") (pintype "bidirectional"))
      (node (ref "U6") (pin "15") (pinfunction "D6_15") (pintype "bidirectional"))
      (node (ref "U6") (pin "17") (pinfunction "D7_17") (pintype "bidirectional"))
      (node (ref "U6") (pin "19") (pinfunction "D8_19") (pintype "bidirectional"))
      (node (ref "U6") (pin "6") (pinfunction "D1_6") (pintype "bidirectional"))
      (node (ref "U6") (pin "8") (pinfunction "D2_8") (pintype "bidirectional"))
      (node (ref "U9") (pin "10") (pinfunction "D3_10") (pintype "bidirectional"))
      (node (ref "U9") (pin "12") (pinfunction "D4_12") (pintype "bidirectional"))
      (node (ref "U9") (pin "13") (pinfunction "D5_13") (pintype "bidirectional"))
      (node (ref "U9") (pin "15") (pinfunction "D6_15") (pintype "bidirectional"))
      (node (ref "U9") (pin "17") (pinfunction "D7_17") (pintype "bidirectional"))
      (node (ref "U9") (pin "19") (pinfunction "D8_19") (pintype "bidirectional"))
      (node (ref "U9") (pin "6") (pinfunction "D1_6") (pintype "bidirectional"))
      (node (ref "U9") (pin "8") (pinfunction "D2_8") (pintype "bidirectional"))
    )
    (net (code "26") (name "LBO") (class "Default")
      (node (ref "R14") (pin "1") (pinfunction "1_1") (pintype "passive"))
      (node (ref "U4") (pin "12") (pinfunction "LBO_12") (pintype "output"))
    )
    (net (code "27") (name "LB_REF") (class "Default")
      (node (ref "R4") (pin "1") (pinfunction "1_1") (pintype "passive"))
      (node (ref "R5") (pin "2") (pinfunction "2_2") (pintype "passive"))
      (node (ref "U4") (pin "9") (pinfunction "LBI_9") (pintype "input"))
    )
    (net (code "28") (name "Net-(JP5-Pad2)") (class "Default")
      (node (ref "JP5") (pin "2") (pinfunction "2_2") (pintype "passive"))
      (node (ref "X3") (pin "G1") (pinfunction "G1_G1") (pintype "passive"))
      (node (ref "X3") (pin "G2") (pinfunction "G2_G2") (pintype "passive"))
    )
    (net (code "29") (name "Net-(L1-Pad2)") (class "Default")
      (node (ref "L1") (pin "2") (pinfunction "2_2") (pintype "passive"))
      (node (ref "U4") (pin "3") (pinfunction "SW_3") (pintype "input"))
      (node (ref "U4") (pin "4") (pinfunction "SW_4") (pintype "input"))
    )
    (net (code "30") (name "Net-(LED1-PadC)") (class "Default")
      (node (ref "LED1") (pin "C") (pinfunction "C_C") (pintype "passive"))
      (node (ref "R1") (pin "2") (pinfunction "2_2") (pintype "passive"))
    )
    (net (code "31") (name "Net-(LED2-PadA)") (class "Default")
      (node (ref "LED2") (pin "A") (pinfunction "A_A") (pintype "passive"))
      (node (ref "R2") (pin "2") (pinfunction "2_2") (pintype "passive"))
    )
    (net (code "32") (name "Net-(LED3-PadC)") (class "Default")
      (node (ref "LED3") (pin "C") (pinfunction "C_C") (pintype "passive"))
      (node (ref "R11") (pin "1") (pinfunction "1_1") (pintype "passive"))
    )
    (net (code "33") (name "Net-(LED4-PadA)") (class "Default")
      (node (ref "LED4") (pin "A") (pinfunction "A_A") (pintype "passive"))
      (node (ref "R16") (pin "2") (pinfunction "2_2") (pintype "passive"))
    )
    (net (code "34") (name "Net-(R8-Pad1)") (class "Default")
      (node (ref "R8") (pin "1") (pinfunction "1_1") (pintype "passive"))
      (node (ref "R9") (pin "2") (pinfunction "2_2") (pintype "passive"))
    )
    (net (code "35") (name "Net-(R14-Pad2)") (class "Default")
      (node (ref "R14") (pin "2") (pinfunction "2_2") (pintype "passive"))
      (node (ref "R15") (pin "1") (pinfunction "1_1") (pintype "passive"))
      (node (ref "T1") (pin "B") (pinfunction "B_B") (pintype "passive"))
    )
    (net (code "36") (name "Net-(R16-Pad1)") (class "Default")
      (node (ref "R16") (pin "1") (pinfunction "1_1") (pintype "passive"))
      (node (ref "T1") (pin "C") (pinfunction "C_C") (pintype "passive"))
    )
    (net (code "37") (name "Net-(U1-PROG)") (class "Default")
      (node (ref "R3") (pin "2") (pinfunction "2_2") (pintype "passive"))
      (node (ref "U1") (pin "5") (pinfunction "PROG_5") (pintype "input"))
    )
    (net (code "38") (name "Net-(U1-STAT)") (class "Default")
      (node (ref "R1") (pin "1") (pinfunction "1_1") (pintype "passive"))
      (node (ref "R2") (pin "1") (pinfunction "1_1") (pintype "passive"))
      (node (ref "U1") (pin "1") (pinfunction "STAT_1") (pintype "output"))
    )
    (net (code "39") (name "Net-(U8-BYP)") (class "Default")
      (node (ref "C14") (pin "2") (pinfunction "2_2") (pintype "passive"))
      (node (ref "U8") (pin "6") (pinfunction "BYP_6") (pintype "input"))
    )
    (net (code "40") (name "Net-(U8-SENSE)") (class "Default")
      (node (ref "C14") (pin "1") (pinfunction "1_1") (pintype "passive"))
      (node (ref "U8") (pin "3") (pinfunction "OUT_3") (pintype "passive"))
      (node (ref "U8") (pin "5") (pinfunction "SENSE_5") (pintype "input"))
    )
    (net (code "41") (name "OUT_1") (class "Default")
      (node (ref "U2") (pin "5") (pinfunction "S1_5") (pintype "bidirectional"))
      (node (ref "U3") (pin "5") (pinfunction "S1_5") (pintype "bidirectional"))
      (node (ref "X4") (pin "1") (pinfunction "1_1") (pintype "passive"))
      (node (ref "X5") (pin "1") (pinfunction "1_1") (pintype "passive"))
    )
    (net (code "42") (name "OUT_2") (class "Default")
      (node (ref "U2") (pin "7") (pinfunction "S2_7") (pintype "bidirectional"))
      (node (ref "U3") (pin "7") (pinfunction "S2_7") (pintype "bidirectional"))
      (node (ref "X4") (pin "2") (pinfunction "2_2") (pintype "passive"))
      (node (ref "X5") (pin "2") (pinfunction "2_2") (pintype "passive"))
    )
    (net (code "43") (name "OUT_3") (class "Default")
      (node (ref "U2") (pin "9") (pinfunction "S3_9") (pintype "bidirectional"))
      (node (ref "U3") (pin "9") (pinfunction "S3_9") (pintype "bidirectional"))
      (node (ref "X4") (pin "3") (pinfunction "3_3") (pintype "passive"))
      (node (ref "X5") (pin "3") (pinfunction "3_3") (pintype "passive"))
    )
    (net (code "44") (name "OUT_4") (class "Default")
      (node (ref "U2") (pin "11") (pinfunction "S4_11") (pintype "bidirectional"))
      (node (ref "U3") (pin "11") (pinfunction "S4_11") (pintype "bidirectional"))
      (node (ref "X4") (pin "4") (pinfunction "4_4") (pintype "passive"))
      (node (ref "X5") (pin "4") (pinfunction "4_4") (pintype "passive"))
    )
    (net (code "45") (name "OUT_5") (class "Default")
      (node (ref "U2") (pin "14") (pinfunction "S5_14") (pintype "bidirectional"))
      (node (ref "U3") (pin "14") (pinfunction "S5_14") (pintype "bidirectional"))
      (node (ref "X4") (pin "5") (pinfunction "5_5") (pintype "passive"))
      (node (ref "X5") (pin "5") (pinfunction "5_5") (pintype "passive"))
    )
    (net (code "46") (name "OUT_6") (class "Default")
      (node (ref "U2") (pin "16") (pinfunction "S6_16") (pintype "bidirectional"))
      (node (ref "U3") (pin "16") (pinfunction "S6_16") (pintype "bidirectional"))
      (node (ref "X4") (pin "6") (pinfunction "6_6") (pintype "passive"))
      (node (ref "X5") (pin "6") (pinfunction "6_6") (pintype "passive"))
    )
    (net (code "47") (name "OUT_7") (class "Default")
      (node (ref "U2") (pin "18") (pinfunction "S7_18") (pintype "bidirectional"))
      (node (ref "U3") (pin "18") (pinfunction "S7_18") (pintype "bidirectional"))
      (node (ref "X4") (pin "7") (pinfunction "7_7") (pintype "passive"))
      (node (ref "X5") (pin "7") (pinfunction "7_7") (pintype "passive"))
    )
    (net (code "48") (name "OUT_8") (class "Default")
      (node (ref "U2") (pin "20") (pinfunction "S8_20") (pintype "bidirectional"))
      (node (ref "U3") (pin "20") (pinfunction "S8_20") (pintype "bidirectional"))
      (node (ref "X4") (pin "8") (pinfunction "8_8") (pintype "passive"))
      (node (ref "X5") (pin "8") (pinfunction "8_8") (pintype "passive"))
    )
    (net (code "49") (name "OUT_9") (class "Default")
      (node (ref "U5") (pin "5") (pinfunction "S1_5") (pintype "bidirectional"))
      (node (ref "U6") (pin "5") (pinfunction "S1_5") (pintype "bidirectional"))
      (node (ref "X4") (pin "9") (pinfunction "9_9") (pintype "passive"))
      (node (ref "X5") (pin "9") (pinfunction "9_9") (pintype "passive"))
    )
    (net (code "50") (name "OUT_10") (class "Default")
      (node (ref "U5") (pin "7") (pinfunction "S2_7") (pintype "bidirectional"))
      (node (ref "U6") (pin "7") (pinfunction "S2_7") (pintype "bidirectional"))
      (node (ref "X4") (pin "10") (pinfunction "10_10") (pintype "passive"))
      (node (ref "X5") (pin "10") (pinfunction "10_10") (pintype "passive"))
    )
    (net (code "51") (name "OUT_11") (class "Default")
      (node (ref "U5") (pin "9") (pinfunction "S3_9") (pintype "bidirectional"))
      (node (ref "U6") (pin "9") (pinfunction "S3_9") (pintype "bidirectional"))
      (node (ref "X4") (pin "11") (pinfunction "11_11") (pintype "passive"))
      (node (ref "X5") (pin "11") (pinfunction "11_11") (pintype "passive"))
    )
    (net (code "52") (name "OUT_12") (class "Default")
      (node (ref "U5") (pin "11") (pinfunction "S4_11") (pintype "bidirectional"))
      (node (ref "U6") (pin "11") (pinfunction "S4_11") (pintype "bidirectional"))
      (node (ref "X4") (pin "12") (pinfunction "12_12") (pintype "passive"))
      (node (ref "X5") (pin "12") (pinfunction "12_12") (pintype "passive"))
    )
    (net (code "53") (name "OUT_13") (class "Default")
      (node (ref "U5") (pin "14") (pinfunction "S5_14") (pintype "bidirectional"))
      (node (ref "U6") (pin "14") (pinfunction "S5_14") (pintype "bidirectional"))
      (node (ref "X4") (pin "13") (pinfunction "13_13") (pintype "passive"))
      (node (ref "X5") (pin "13") (pinfunction "13_13") (pintype "passive"))
    )
    (net (code "54") (name "OUT_14") (class "Default")
      (node (ref "U5") (pin "16") (pinfunction "S6_16") (pintype "bidirectional"))
      (node (ref "U6") (pin "16") (pinfunction "S6_16") (pintype "bidirectional"))
      (node (ref "X4") (pin "14") (pinfunction "14_14") (pintype "passive"))
      (node (ref "X5") (pin "14") (pinfunction "14_14") (pintype "passive"))
    )
    (net (code "55") (name "OUT_15") (class "Default")
      (node (ref "U5") (pin "18") (pinfunction "S7_18") (pintype "bidirectional"))
      (node (ref "U6") (pin "18") (pinfunction "S7_18") (pintype "bidirectional"))
      (node (ref "X4") (pin "15") (pinfunction "15_15") (pintype "passive"))
      (node (ref "X5") (pin "15") (pinfunction "15_15") (pintype "passive"))
    )
    (net (code "56") (name "OUT_16") (class "Default")
      (node (ref "U5") (pin "20") (pinfunction "S8_20") (pintype "bidirectional"))
      (node (ref "U6") (pin "20") (pinfunction "S8_20") (pintype "bidirectional"))
      (node (ref "X4") (pin "16") (pinfunction "16_16") (pintype "passive"))
      (node (ref "X5") (pin "16") (pinfunction "16_16") (pintype "passive"))
    )
    (net (code "57") (name "OUT_17") (class "Default")
      (node (ref "U7") (pin "5") (pinfunction "S1_5") (pintype "bidirectional"))
      (node (ref "U9") (pin "5") (pinfunction "S1_5") (pintype "bidirectional"))
      (node (ref "X4") (pin "17") (pinfunction "17_17") (pintype "passive"))
      (node (ref "X5") (pin "17") (pinfunction "17_17") (pintype "passive"))
    )
    (net (code "58") (name "OUT_18") (class "Default")
      (node (ref "U7") (pin "7") (pinfunction "S2_7") (pintype "bidirectional"))
      (node (ref "U9") (pin "7") (pinfunction "S2_7") (pintype "bidirectional"))
      (node (ref "X4") (pin "18") (pinfunction "18_18") (pintype "passive"))
      (node (ref "X5") (pin "18") (pinfunction "18_18") (pintype "passive"))
    )
    (net (code "59") (name "OUT_19") (class "Default")
      (node (ref "U7") (pin "9") (pinfunction "S3_9") (pintype "bidirectional"))
      (node (ref "U9") (pin "9") (pinfunction "S3_9") (pintype "bidirectional"))
      (node (ref "X4") (pin "19") (pinfunction "19_19") (pintype "passive"))
      (node (ref "X5") (pin "19") (pinfunction "19_19") (pintype "passive"))
    )
    (net (code "60") (name "OUT_20") (class "Default")
      (node (ref "U7") (pin "11") (pinfunction "S4_11") (pintype "bidirectional"))
      (node (ref "U9") (pin "11") (pinfunction "S4_11") (pintype "bidirectional"))
      (node (ref "X4") (pin "20") (pinfunction "20_20") (pintype "passive"))
      (node (ref "X5") (pin "20") (pinfunction "20_20") (pintype "passive"))
    )
    (net (code "61") (name "OUT_21") (class "Default")
      (node (ref "U7") (pin "14") (pinfunction "S5_14") (pintype "bidirectional"))
      (node (ref "U9") (pin "14") (pinfunction "S5_14") (pintype "bidirectional"))
      (node (ref "X4") (pin "21") (pinfunction "21_21") (pintype "passive"))
      (node (ref "X5") (pin "21") (pinfunction "21_21") (pintype "passive"))
    )
    (net (code "62") (name "OUT_22") (class "Default")
      (node (ref "U7") (pin "16") (pinfunction "S6_16") (pintype "bidirectional"))
      (node (ref "U9") (pin "16") (pinfunction "S6_16") (pintype "bidirectional"))
      (node (ref "X4") (pin "22") (pinfunction "22_22") (pintype "passive"))
      (node (ref "X5") (pin "22") (pinfunction "22_22") (pintype "passive"))
    )
    (net (code "63") (name "OUT_23") (class "Default")
      (node (ref "U7") (pin "18") (pinfunction "S7_18") (pintype "bidirectional"))
      (node (ref "U9") (pin "18") (pinfunction "S7_18") (pintype "bidirectional"))
      (node (ref "X4") (pin "23") (pinfunction "23_23") (pintype "passive"))
      (node (ref "X5") (pin "23") (pinfunction "23_23") (pintype "passive"))
    )
    (net (code "64") (name "OUT_24") (class "Default")
      (node (ref "U7") (pin "20") (pinfunction "S8_20") (pintype "bidirectional"))
      (node (ref "U9") (pin "20") (pinfunction "S8_20") (pintype "bidirectional"))
      (node (ref "X4") (pin "24") (pinfunction "24_24") (pintype "passive"))
      (node (ref "X5") (pin "24") (pinfunction "24_24") (pintype "passive"))
    )
    (net (code "65") (name "OUT_25") (class "Default")
      (node (ref "U10") (pin "5") (pinfunction "S1_5") (pintype "bidirectional"))
      (node (ref "U11") (pin "5") (pinfunction "S1_5") (pintype "bidirectional"))
      (node (ref "X4") (pin "25") (pinfunction "25_25") (pintype "passive"))
      (node (ref "X5") (pin "25") (pinfunction "25_25") (pintype "passive"))
    )
    (net (code "66") (name "OUT_26") (class "Default")
      (node (ref "U10") (pin "7") (pinfunction "S2_7") (pintype "bidirectional"))
      (node (ref "U11") (pin "7") (pinfunction "S2_7") (pintype "bidirectional"))
      (node (ref "X4") (pin "26") (pinfunction "26_26") (pintype "passive"))
      (node (ref "X5") (pin "26") (pinfunction "26_26") (pintype "passive"))
    )
    (net (code "67") (name "OUT_27") (class "Default")
      (node (ref "U10") (pin "9") (pinfunction "S3_9") (pintype "bidirectional"))
      (node (ref "U11") (pin "9") (pinfunction "S3_9") (pintype "bidirectional"))
      (node (ref "X4") (pin "27") (pinfunction "27_27") (pintype "passive"))
      (node (ref "X5") (pin "27") (pinfunction "27_27") (pintype "passive"))
    )
    (net (code "68") (name "OUT_28") (class "Default")
      (node (ref "U10") (pin "11") (pinfunction "S4_11") (pintype "bidirectional"))
      (node (ref "U11") (pin "11") (pinfunction "S4_11") (pintype "bidirectional"))
      (node (ref "X4") (pin "28") (pinfunction "28_28") (pintype "passive"))
      (node (ref "X5") (pin "28") (pinfunction "28_28") (pintype "passive"))
    )
    (net (code "69") (name "OUT_29") (class "Default")
      (node (ref "U10") (pin "14") (pinfunction "S5_14") (pintype "bidirectional"))
      (node (ref "U11") (pin "14") (pinfunction "S5_14") (pintype "bidirectional"))
      (node (ref "X4") (pin "29") (pinfunction "29_29") (pintype "passive"))
      (node (ref "X5") (pin "29") (pinfunction "29_29") (pintype "passive"))
    )
    (net (code "70") (name "OUT_30") (class "Default")
      (node (ref "U10") (pin "16") (pinfunction "S6_16") (pintype "bidirectional"))
      (node (ref "U11") (pin "16") (pinfunction "S6_16") (pintype "bidirectional"))
      (node (ref "X4") (pin "30") (pinfunction "30_30") (pintype "passive"))
      (node (ref "X5") (pin "30") (pinfunction "30_30") (pintype "passive"))
    )
    (net (code "71") (name "OUT_31") (class "Default")
      (node (ref "U10") (pin "18") (pinfunction "S7_18") (pintype "bidirectional"))
      (node (ref "U11") (pin "18") (pinfunction "S7_18") (pintype "bidirectional"))
      (node (ref "X4") (pin "31") (pinfunction "31_31") (pintype "passive"))
      (node (ref "X5") (pin "31") (pinfunction "31_31") (pintype "passive"))
    )
    (net (code "72") (name "OUT_32") (class "Default")
      (node (ref "U10") (pin "20") (pinfunction "S8_20") (pintype "bidirectional"))
      (node (ref "U11") (pin "20") (pinfunction "S8_20") (pintype "bidirectional"))
      (node (ref "X4") (pin "32") (pinfunction "32_32") (pintype "passive"))
      (node (ref "X5") (pin "32") (pinfunction "32_32") (pintype "passive"))
    )
    (net (code "73") (name "OUT_33") (class "Default")
      (node (ref "U13") (pin "5") (pinfunction "S1_5") (pintype "bidirectional"))
      (node (ref "U14") (pin "5") (pinfunction "S1_5") (pintype "bidirectional"))
      (node (ref "X4") (pin "33") (pinfunction "33_33") (pintype "passive"))
      (node (ref "X5") (pin "33") (pinfunction "33_33") (pintype "passive"))
    )
    (net (code "74") (name "OUT_34") (class "Default")
      (node (ref "U13") (pin "7") (pinfunction "S2_7") (pintype "bidirectional"))
      (node (ref "U14") (pin "7") (pinfunction "S2_7") (pintype "bidirectional"))
      (node (ref "X4") (pin "34") (pinfunction "34_34") (pintype "passive"))
      (node (ref "X5") (pin "34") (pinfunction "34_34") (pintype "passive"))
    )
    (net (code "75") (name "OUT_35") (class "Default")
      (node (ref "U13") (pin "9") (pinfunction "S3_9") (pintype "bidirectional"))
      (node (ref "U14") (pin "9") (pinfunction "S3_9") (pintype "bidirectional"))
      (node (ref "X4") (pin "35") (pinfunction "35_35") (pintype "passive"))
      (node (ref "X5") (pin "35") (pinfunction "35_35") (pintype "passive"))
    )
    (net (code "76") (name "OUT_36") (class "Default")
      (node (ref "U13") (pin "11") (pinfunction "S4_11") (pintype "bidirectional"))
      (node (ref "U14") (pin "11") (pinfunction "S4_11") (pintype "bidirectional"))
      (node (ref "X4") (pin "36") (pinfunction "36_36") (pintype "passive"))
      (node (ref "X5") (pin "36") (pinfunction "36_36") (pintype "passive"))
    )
    (net (code "77") (name "OUT_37") (class "Default")
      (node (ref "U13") (pin "14") (pinfunction "S5_14") (pintype "bidirectional"))
      (node (ref "U14") (pin "14") (pinfunction "S5_14") (pintype "bidirectional"))
      (node (ref "X4") (pin "37") (pinfunction "37_37") (pintype "passive"))
      (node (ref "X5") (pin "37") (pinfunction "37_37") (pintype "passive"))
    )
    (net (code "78") (name "RESET_IN") (class "Default")
      (node (ref "R31") (pin "2") (pinfunction "2_2") (pintype "passive"))
      (node (ref "U15") (pin "3") (pinfunction "VIA_3") (pintype "passive"))
      (node (ref "X2") (pin "8") (pinfunction "8_8") (pintype "passive"))
    )
    (net (code "79") (name "SCLK") (class "Default")
      (node (ref "U$1") (pin "19") (pinfunction "19_19") (pintype "passive"))
      (node (ref "U10") (pin "1") (pinfunction "SCLK_1") (pintype "input"))
      (node (ref "U11") (pin "1") (pinfunction "SCLK_1") (pintype "input"))
      (node (ref "U13") (pin "1") (pinfunction "SCLK_1") (pintype "input"))
      (node (ref "U14") (pin "1") (pinfunction "SCLK_1") (pintype "input"))
      (node (ref "U2") (pin "1") (pinfunction "SCLK_1") (pintype "input"))
      (node (ref "U3") (pin "1") (pinfunction "SCLK_1") (pintype "input"))
      (node (ref "U5") (pin "1") (pinfunction "SCLK_1") (pintype "input"))
      (node (ref "U6") (pin "1") (pinfunction "SCLK_1") (pintype "input"))
      (node (ref "U7") (pin "1") (pinfunction "SCLK_1") (pintype "input"))
      (node (ref "U9") (pin "1") (pinfunction "SCLK_1") (pintype "input"))
      (node (ref "X3") (pin "2") (pinfunction "2_2") (pintype "passive"))
    )
    (net (code "80") (name "SCLK_BRD") (class "Default")
      (node (ref "U$1") (pin "9") (pinfunction "9_9") (pintype "passive"))
      (node (ref "U12") (pin "11") (pinfunction "VOD_11") (pintype "passive"))
    )
    (net (code "81") (name "SCLK_DCHN") (class "Default")
      (node (ref "R35") (pin "2") (pinfunction "2_2") (pintype "passive"))
      (node (ref "U$1") (pin "10") (pinfunction "10_10") (pintype "passive"))
      (node (ref "X6") (pin "2") (pinfunction "2_2") (pintype "passive"))
    )
    (net (code "82") (name "SCLK_IN") (class "Default")
      (node (ref "R26") (pin "1") (pinfunction "1_1") (pintype "passive"))
      (node (ref "U12") (pin "6") (pinfunction "VID_6") (pintype "passive"))
      (node (ref "X2") (pin "2") (pinfunction "2_2") (pintype "passive"))
    )
    (net (code "83") (name "SYNC_IN") (class "Default")
      (node (ref "R28") (pin "2") (pinfunction "2_2") (pintype "passive"))
      (node (ref "U12") (pin "3") (pinfunction "VIA_3") (pintype "passive"))
      (node (ref "X2") (pin "4") (pinfunction "4_4") (pintype "passive"))
    )
    (net (code "84") (name "TEST_1_IN") (class "Default")
      (node (ref "R27") (pin "2") (pinfunction "2_2") (pintype "passive"))
      (node (ref "U15") (pin "5") (pinfunction "VOC_5") (pintype "passive"))
      (node (ref "X2") (pin "5") (pinfunction "5_5") (pintype "passive"))
    )
    (net (code "85") (name "TEST_2") (class "Default")
      (node (ref "R24") (pin "2") (pinfunction "2_2") (pintype "passive"))
      (node (ref "U$1") (pin "21") (pinfunction "21_21") (pintype "passive"))
      (node (ref "U13") (pin "18") (pinfunction "S7_18") (pintype "bidirectional"))
      (node (ref "U14") (pin "18") (pinfunction "S7_18") (pintype "bidirectional"))
      (node (ref "X3") (pin "1") (pinfunction "1_1") (pintype "passive"))
    )
    (net (code "86") (name "TEST_2_BRD") (class "Default")
      (node (ref "U$1") (pin "13") (pinfunction "13_13") (pintype "passive"))
      (node (ref "U15") (pin "11") (pinfunction "VID_11") (pintype "passive"))
    )
    (net (code "87") (name "TEST_2_DCHN") (class "Default")
      (node (ref "R34") (pin "2") (pinfunction "2_2") (pintype "passive"))
      (node (ref "U$1") (pin "14") (pinfunction "14_14") (pintype "passive"))
      (node (ref "X6") (pin "1") (pinfunction "1_1") (pintype "passive"))
    )
    (net (code "88") (name "TEST_2_IN") (class "Default")
      (node (ref "R25") (pin "1") (pinfunction "1_1") (pintype "passive"))
      (node (ref "U15") (pin "6") (pinfunction "VOD_6") (pintype "passive"))
      (node (ref "X2") (pin "1") (pinfunction "1_1") (pintype "passive"))
    )
    (net (code "89") (name "VBATT_A") (class "Default")
      (node (ref "C2") (pin "1") (pinfunction "1_1") (pintype "passive"))
      (node (ref "D2") (pin "C") (pinfunction "C_C") (pintype "passive"))
      (node (ref "JP4") (pin "1") (pinfunction "1_1") (pintype "passive"))
      (node (ref "U1") (pin "3") (pinfunction "VBAT_3") (pintype "power_in"))
      (node (ref "X7") (pin "2") (pinfunction "S_2") (pintype "passive"))
    )
    (net (code "90") (name "VBATT_B") (class "Default")
      (node (ref "C3") (pin "1") (pinfunction "1_1") (pintype "passive"))
      (node (ref "C4") (pin "1") (pinfunction "1_1") (pintype "passive"))
      (node (ref "JP4") (pin "2") (pinfunction "2_2") (pintype "passive"))
      (node (ref "L1") (pin "1") (pinfunction "1_1") (pintype "passive"))
      (node (ref "R15") (pin "2") (pinfunction "2_2") (pintype "passive"))
      (node (ref "R4") (pin "2") (pinfunction "2_2") (pintype "passive"))
      (node (ref "T1") (pin "E") (pinfunction "E_E") (pintype "passive"))
      (node (ref "U4") (pin "11") (pinfunction "EN_11") (pintype "input"))
      (node (ref "U4") (pin "8") (pinfunction "VBAT_8") (pintype "input"))
    )
    (net (code "91") (name "VDD") (class "Default")
      (node (ref "C12") (pin "2") (pinfunction "2_2") (pintype "passive"))
      (node (ref "C13") (pin "2") (pinfunction "2_2") (pintype "passive"))
      (node (ref "C16") (pin "2") (pinfunction "2_2") (pintype "passive"))
      (node (ref "C17") (pin "2") (pinfunction "2_2") (pintype "passive"))
      (node (ref "C22") (pin "2") (pinfunction "2_2") (pintype "passive"))
      (node (ref "C23") (pin "2") (pinfunction "2_2") (pintype "passive"))
      (node (ref "C5") (pin "2") (pinfunction "2_2") (pintype "passive"))
      (node (ref "C6") (pin "2") (pinfunction "2_2") (pintype "passive"))
      (node (ref "C7") (pin "2") (pinfunction "2_2") (pintype "passive"))
      (node (ref "C8") (pin "2") (pinfunction "2_2") (pintype "passive"))
      (node (ref "R12") (pin "2") (pinfunction "2_2") (pintype "passive"))
      (node (ref "R13") (pin "2") (pinfunction "2_2") (pintype "passive"))
      (node (ref "R17") (pin "2") (pinfunction "2_2") (pintype "passive"))
      (node (ref "R18") (pin "2") (pinfunction "2_2") (pintype "passive"))
      (node (ref "R19") (pin "2") (pinfunction "2_2") (pintype "passive"))
      (node (ref "R20") (pin "2") (pinfunction "2_2") (pintype "passive"))
      (node (ref "R21") (pin "2") (pinfunction "2_2") (pintype "passive"))
      (node (ref "R22") (pin "2") (pinfunction "2_2") (pintype "passive"))
      (node (ref "R6") (pin "2") (pinfunction "2_2") (pintype "passive"))
      (node (ref "R7") (pin "2") (pinfunction "2_2") (pintype "passive"))
      (node (ref "U$1") (pin "15") (pinfunction "15_15") (pintype "passive"))
      (node (ref "U10") (pin "2") (pinfunction "VDD_2") (pintype "power_in"))
      (node (ref "U11") (pin "2") (pinfunction "VDD_2") (pintype "power_in"))
      (node (ref "U13") (pin "17") (pinfunction "D7_17") (pintype "bidirectional"))
      (node (ref "U13") (pin "2") (pinfunction "VDD_2") (pintype "power_in"))
      (node (ref "U14") (pin "17") (pinfunction "D7_17") (pintype "bidirectional"))
      (node (ref "U14") (pin "2") (pinfunction "VDD_2") (pintype "power_in"))
      (node (ref "U2") (pin "2") (pinfunction "VDD_2") (pintype "power_in"))
      (node (ref "U3") (pin "2") (pinfunction "VDD_2") (pintype "power_in"))
      (node (ref "U5") (pin "2") (pinfunction "VDD_2") (pintype "power_in"))
      (node (ref "U6") (pin "2") (pinfunction "VDD_2") (pintype "power_in"))
      (node (ref "U7") (pin "2") (pinfunction "VDD_2") (pintype "power_in"))
      (node (ref "U9") (pin "2") (pinfunction "VDD_2") (pintype "power_in"))
      (node (ref "X3") (pin "5") (pinfunction "5_5") (pintype "passive"))
      (node (ref "X3") (pin "9") (pinfunction "9_9") (pintype "passive"))
    )
    (net (code "92") (name "VDD_BRD") (class "Default")
      (node (ref "C15") (pin "+") (pinfunction "+_+") (pintype "passive"))
      (node (ref "C18") (pin "1") (pinfunction "1_1") (pintype "passive"))
      (node (ref "C19") (pin "1") (pinfunction "1_1") (pintype "passive"))
      (node (ref "C24") (pin "1") (pinfunction "1_1") (pintype "passive"))
      (node (ref "C25") (pin "1") (pinfunction "1_1") (pintype "passive"))
      (node (ref "R23") (pin "2") (pinfunction "2_2") (pintype "passive"))
      (node (ref "U$1") (pin "1") (pinfunction "1_1") (pintype "passive"))
      (node (ref "U12") (pin "16") (pinfunction "VDD2_16") (pintype "power_in"))
      (node (ref "U15") (pin "12") (pinfunction "VIC_12") (pintype "passive"))
      (node (ref "U15") (pin "16") (pinfunction "VDD2_16") (pintype "power_in"))
      (node (ref "U8") (pin "2") (pinfunction "OUT_2") (pintype "passive"))
    )
    (net (code "93") (name "VDD_DCHN") (class "Default")
      (node (ref "R30") (pin "2") (pinfunction "2_2") (pintype "passive"))
      (node (ref "U$1") (pin "2") (pinfunction "2_2") (pintype "passive"))
      (node (ref "X6") (pin "5") (pinfunction "5_5") (pintype "passive"))
      (node (ref "X6") (pin "9") (pinfunction "9_9") (pintype "passive"))
    )
    (net (code "94") (name "VREG") (class "Default")
      (node (ref "C10") (pin "+") (pinfunction "+_+") (pintype "passive"))
      (node (ref "C11") (pin "1") (pinfunction "1_1") (pintype "passive"))
      (node (ref "C9") (pin "1") (pinfunction "1_1") (pintype "passive"))
      (node (ref "LED3") (pin "A") (pinfunction "A_A") (pintype "passive"))
      (node (ref "R8") (pin "2") (pinfunction "2_2") (pintype "passive"))
      (node (ref "U4") (pin "1") (pinfunction "VOUT_1") (pintype "power_in"))
      (node (ref "U4") (pin "15") (pinfunction "VOUT_15") (pintype "power_in"))
      (node (ref "U4") (pin "16") (pinfunction "VOUT_16") (pintype "power_in"))
      (node (ref "U8") (pin "10") (pinfunction "IN_10") (pintype "input"))
      (node (ref "U8") (pin "11") (pinfunction "IN_11") (pintype "input"))
      (node (ref "U8") (pin "8") (pinfunction "~{SHDN}_8") (pintype "input"))
    )
    (net (code "95") (name "VSET") (class "Default")
      (node (ref "R10") (pin "2") (pinfunction "2_2") (pintype "passive"))
      (node (ref "R9") (pin "1") (pinfunction "1_1") (pintype "passive"))
      (node (ref "U4") (pin "14") (pinfunction "FB_14") (pintype "input"))
    )
    (net (code "96") (name "unconnected-(U15-VIB-Pad4)") (class "Default")
      (node (ref "U15") (pin "4") (pinfunction "VIB_4") (pintype "passive"))
    )
    (net (code "97") (name "unconnected-(U15-VOB-Pad13)") (class "Default")
      (node (ref "U15") (pin "13") (pinfunction "VOB_13") (pintype "passive"))
    )
    (net (code "98") (name "unconnected-(X1-Pad2)") (class "Default")
      (node (ref "X1") (pin "2") (pinfunction "2_2") (pintype "input"))
    )
    (net (code "99") (name "unconnected-(X1-Pad3)") (class "Default")
      (node (ref "X1") (pin "3") (pinfunction "3_3") (pintype "input"))
    )
    (net (code "100") (name "unconnected-(X1-Pad4)") (class "Default")
      (node (ref "X1") (pin "4") (pinfunction "4_4") (pintype "input"))
    )
    (net (code "101") (name "unconnected-(X2-PadG1)") (class "Default")
      (node (ref "X2") (pin "G1") (pinfunction "G1_G1") (pintype "passive"))
    )
    (net (code "102") (name "unconnected-(X2-PadG2)") (class "Default")
      (node (ref "X2") (pin "G2") (pinfunction "G2_G2") (pintype "passive"))
    )
    (net (code "103") (name "unconnected-(X4-PadG1)") (class "Default")
      (node (ref "X4") (pin "G1") (pinfunction "G1_G1") (pintype "passive"))
    )
    (net (code "104") (name "unconnected-(X4-PadG2)") (class "Default")
      (node (ref "X4") (pin "G2") (pinfunction "G2_G2") (pintype "passive"))
    )
    (net (code "105") (name "unconnected-(X5-PadG1)") (class "Default")
      (node (ref "X5") (pin "G1") (pinfunction "G1_G1") (pintype "passive"))
    )
    (net (code "106") (name "unconnected-(X5-PadG2)") (class "Default")
      (node (ref "X5") (pin "G2") (pinfunction "G2_G2") (pintype "passive"))
    )
    (net (code "107") (name "~{RESET_BRD}") (class "Default")
      (node (ref "U$1") (pin "11") (pinfunction "11_11") (pintype "passive"))
      (node (ref "U15") (pin "14") (pinfunction "VOA_14") (pintype "passive"))
    )
    (net (code "108") (name "~{RESET_DCHN}") (class "Default")
      (node (ref "R38") (pin "2") (pinfunction "2_2") (pintype "passive"))
      (node (ref "U$1") (pin "12") (pinfunction "12_12") (pintype "passive"))
      (node (ref "X6") (pin "8") (pinfunction "8_8") (pintype "passive"))
    )
    (net (code "109") (name "~{RESET}") (class "Default")
      (node (ref "U$1") (pin "20") (pinfunction "20_20") (pintype "passive"))
      (node (ref "U10") (pin "23") (pinfunction "~{RESET}_23") (pintype "input"))
      (node (ref "U11") (pin "23") (pinfunction "~{RESET}_23") (pintype "input"))
      (node (ref "U13") (pin "23") (pinfunction "~{RESET}_23") (pintype "input"))
      (node (ref "U14") (pin "23") (pinfunction "~{RESET}_23") (pintype "input"))
      (node (ref "U2") (pin "23") (pinfunction "~{RESET}_23") (pintype "input"))
      (node (ref "U3") (pin "23") (pinfunction "~{RESET}_23") (pintype "input"))
      (node (ref "U5") (pin "23") (pinfunction "~{RESET}_23") (pintype "input"))
      (node (ref "U6") (pin "23") (pinfunction "~{RESET}_23") (pintype "input"))
      (node (ref "U7") (pin "23") (pinfunction "~{RESET}_23") (pintype "input"))
      (node (ref "U9") (pin "23") (pinfunction "~{RESET}_23") (pintype "input"))
      (node (ref "X3") (pin "8") (pinfunction "8_8") (pintype "passive"))
    )
    (net (code "110") (name "~{SYNC_BRD}") (class "Default")
      (node (ref "U$1") (pin "3") (pinfunction "3_3") (pintype "passive"))
      (node (ref "U12") (pin "14") (pinfunction "VOA_14") (pintype "passive"))
    )
    (net (code "111") (name "~{SYNC_DCHN}") (class "Default")
      (node (ref "R33") (pin "2") (pinfunction "2_2") (pintype "passive"))
      (node (ref "U$1") (pin "4") (pinfunction "4_4") (pintype "passive"))
      (node (ref "X6") (pin "4") (pinfunction "4_4") (pintype "passive"))
    )
    (net (code "112") (name "~{SYNC}") (class "Default")
      (node (ref "U$1") (pin "16") (pinfunction "16_16") (pintype "passive"))
      (node (ref "U10") (pin "24") (pinfunction "~{SYNC}_24") (pintype "input"))
      (node (ref "U11") (pin "24") (pinfunction "~{SYNC}_24") (pintype "input"))
      (node (ref "U13") (pin "24") (pinfunction "~{SYNC}_24") (pintype "input"))
      (node (ref "U14") (pin "24") (pinfunction "~{SYNC}_24") (pintype "input"))
      (node (ref "U2") (pin "24") (pinfunction "~{SYNC}_24") (pintype "input"))
      (node (ref "U3") (pin "24") (pinfunction "~{SYNC}_24") (pintype "input"))
      (node (ref "U5") (pin "24") (pinfunction "~{SYNC}_24") (pintype "input"))
      (node (ref "U6") (pin "24") (pinfunction "~{SYNC}_24") (pintype "input"))
      (node (ref "U7") (pin "24") (pinfunction "~{SYNC}_24") (pintype "input"))
      (node (ref "U9") (pin "24") (pinfunction "~{SYNC}_24") (pintype "input"))
      (node (ref "X3") (pin "4") (pinfunction "4_4") (pintype "passive"))
    )
  )
)
